# Power_supply.net
KiCad netlist of a schematic drawn in Altium Designer
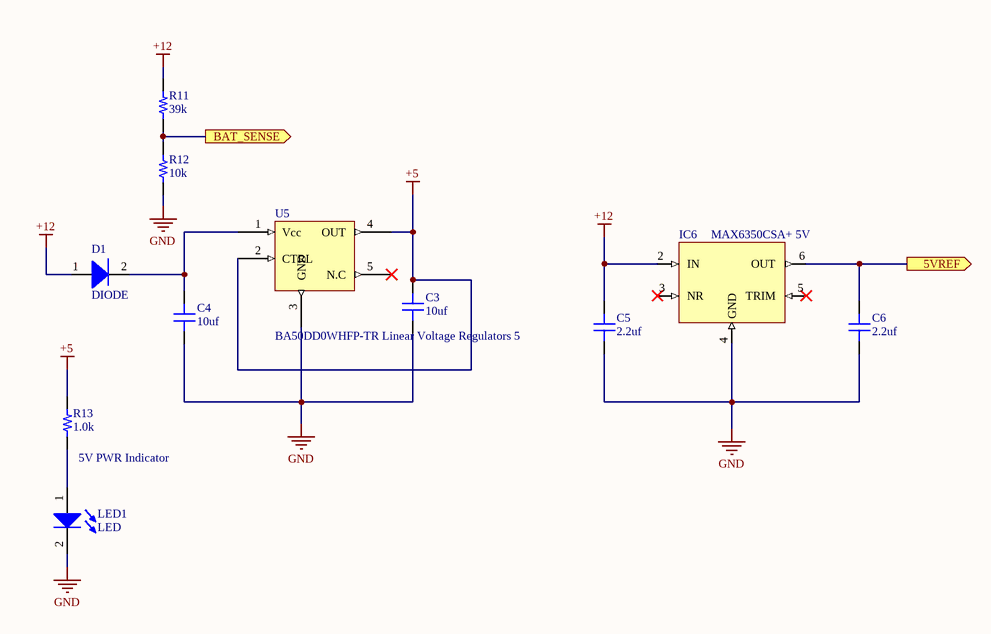
[diagram p0: Power_supply.SchDoc]

(export (version "E")
  (design (tool "Eeschema 10.0.6"))
  (components
    (comp (ref "C3")
      (value "10uf")
      (footprint "CAP 0603/1608")
      (fields
        (field (name "Comment") "Capacitor MLCC 10uf 16V CAP 0603/1608")
        (field (name "CREATED_BY") "Nick Mah")
      )
      (libsource (lib "Altium-Lib") (part "Capacitor"))
    )
    (comp (ref "C4")
      (value "10uf")
      (footprint "CAP 0603/1608")
      (fields
        (field (name "Comment") "Capacitor MLCC 10uf 16V CAP 0603/1608")
        (field (name "CREATED_BY") "Nick Mah")
      )
      (libsource (lib "Altium-Lib") (part "Capacitor"))
    )
    (comp (ref "C5")
      (value "2.2uf")
      (footprint "CAP 0603/1608")
      (fields
        (field (name "Comment") "Capacitor MLCC 2.2uf 16V CAP 0603/1608")
        (field (name "CREATED_BY") "Nick Mah")
      )
      (libsource (lib "Altium-Lib") (part "Capacitor"))
    )
    (comp (ref "C6")
      (value "2.2uf")
      (footprint "CAP 0603/1608")
      (fields
        (field (name "Comment") "Capacitor MLCC 2.2uf 16V CAP 0603/1608")
        (field (name "CREATED_BY") "Nick Mah")
      )
      (libsource (lib "Altium-Lib") (part "Capacitor"))
    )
    (comp (ref "D1")
      (value "DIODE")
      (footprint "SOD123F")
      (description "Diode Super Barrier 40V 1A Surface Mount SOD-123F")
      (fields (field (name "POWER") "40V") (field (name "MFRPARTNO") "1N5819HW1-7-F"))
      (libsource (lib "Altium-Lib") (part "DIODE"))
    )
    (comp (ref "IC6")
      (value "MAX6350CSA+ 5V")
      (footprint "SOIC-8")
      (description "IC VREF SERIES 5V 8SOIC")
      (fields
        (field (name "MFRPARTNO") "MAX6350CSA+")
        (field (name "CREATED_BY") "Albert Panuco")
        (field (name "UPDATED_BY") "Albert Panuco")
      )
      (libsource (lib "Altium-Lib") (part "MAX6350CSA+ 5V"))
    )
    (comp (ref "LED1") (value "LED") (footprint "0805_LED") (libsource (lib "Altium-Lib") (part "LED")))
    (comp (ref "R11")
      (value "39k")
      (footprint "RES 0805/2012")
      (fields
        (field (name "TOLERANCE") "10%")
        (field (name "POWER") "1/10W")
        (field (name "Comment") "Resistor 39k 0805 1/10W 10%")
        (field (name "CREATED_BY") "Nick Mah")
      )
      (libsource (lib "Altium-Lib") (part "Resistor"))
    )
    (comp (ref "R12")
      (value "10k")
      (footprint "RES 0805/2012")
      (fields
        (field (name "TOLERANCE") "10%")
        (field (name "POWER") "1/4W")
        (field (name "Comment") "Resistor 10k 0805 1/4W 10%")
        (field (name "CREATED_BY") "Nick Mah")
      )
      (libsource (lib "Altium-Lib") (part "Resistor"))
    )
    (comp (ref "R13")
      (value "1.0k")
      (footprint "RES 0805/2012")
      (fields
        (field (name "TOLERANCE") "10%")
        (field (name "POWER") "1/10W")
        (field (name "Comment") "Resistor 1.0k 0805 1/10W 10%")
        (field (name "CREATED_BY") "Nick Mah")
      )
      (libsource (lib "Altium-Lib") (part "Resistor"))
    )
    (comp (ref "U5")
      (value "BA50DD0WHFP-TR Linear Voltage Regulators 5")
      (footprint "HRP5")
      (fields (field (name "MFRPARTNO") "BA50DD0WHFP-TR"))
      (libsource (lib "Altium-Lib") (part "BA50DD0WHFP-TR Linear Voltage Regulators 5"))
    )
  )
  (nets
    (net (code "1") (name "+5") (class "Default")
      (node (ref "C3") (pin "2") (pinfunction "2_2") (pintype "passive"))
      (node (ref "R13") (pin "1") (pinfunction "1_1") (pintype "passive"))
      (node (ref "U5") (pin "2") (pinfunction "CTRL_2") (pintype "input"))
      (node (ref "U5") (pin "4") (pinfunction "OUT_4") (pintype "output"))
    )
    (net (code "2") (name "+12") (class "Default")
      (node (ref "C5") (pin "2") (pinfunction "2_2") (pintype "passive"))
      (node (ref "D1") (pin "1") (pinfunction "A_1") (pintype "passive"))
      (node (ref "IC6") (pin "2") (pinfunction "IN_2") (pintype "input"))
      (node (ref "R11") (pin "2") (pinfunction "2_2") (pintype "passive"))
    )
    (net (code "3") (name "/5VREF") (class "Default")
      (node (ref "C6") (pin "2") (pinfunction "2_2") (pintype "passive"))
      (node (ref "IC6") (pin "6") (pinfunction "OUT_6") (pintype "output"))
    )
    (net (code "4") (name "/BAT_SENSE") (class "Default")
      (node (ref "R11") (pin "1") (pinfunction "1_1") (pintype "passive"))
      (node (ref "R12") (pin "2") (pinfunction "2_2") (pintype "passive"))
    )
    (net (code "5") (name "GND") (class "Default")
      (node (ref "C3") (pin "1") (pinfunction "1_1") (pintype "passive"))
      (node (ref "C4") (pin "1") (pinfunction "1_1") (pintype "passive"))
      (node (ref "C5") (pin "1") (pinfunction "1_1") (pintype "passive"))
      (node (ref "C6") (pin "1") (pinfunction "1_1") (pintype "passive"))
      (node (ref "IC6") (pin "4") (pinfunction "GND_4") (pintype "input"))
      (node (ref "LED1") (pin "2") (pinfunction "K_2") (pintype "passive"))
      (node (ref "R12") (pin "1") (pinfunction "1_1") (pintype "passive"))
      (node (ref "U5") (pin "3") (pinfunction "GND_3") (pintype "output"))
    )
    (net (code "6") (name "Net-(D1-K)") (class "Default")
      (node (ref "C4") (pin "2") (pinfunction "2_2") (pintype "passive"))
      (node (ref "D1") (pin "2") (pinfunction "K_2") (pintype "passive"))
      (node (ref "U5") (pin "1") (pinfunction "Vcc_1") (pintype "input"))
    )
    (net (code "7") (name "Net-(LED1-A)") (class "Default")
      (node (ref "LED1") (pin "1") (pinfunction "A_1") (pintype "passive"))
      (node (ref "R13") (pin "2") (pinfunction "2_2") (pintype "passive"))
    )
    (net (code "8") (name "unconnected-(IC6-NR-Pad3)") (class "Default")
      (node (ref "IC6") (pin "3") (pinfunction "NR_3") (pintype "input+no_connect"))
    )
    (net (code "9") (name "unconnected-(IC6-TRIM-Pad5)") (class "Default")
      (node (ref "IC6") (pin "5") (pinfunction "TRIM_5") (pintype "input+no_connect"))
    )
    (net (code "10") (name "unconnected-(U5-N.C-Pad5)") (class "Default")
      (node (ref "U5") (pin "5") (pinfunction "N.C_5") (pintype "output+no_connect"))
    )
  )
)
